# Tactile_SW_v2_0.net
KiCad netlist of a schematic drawn in Altium Designer
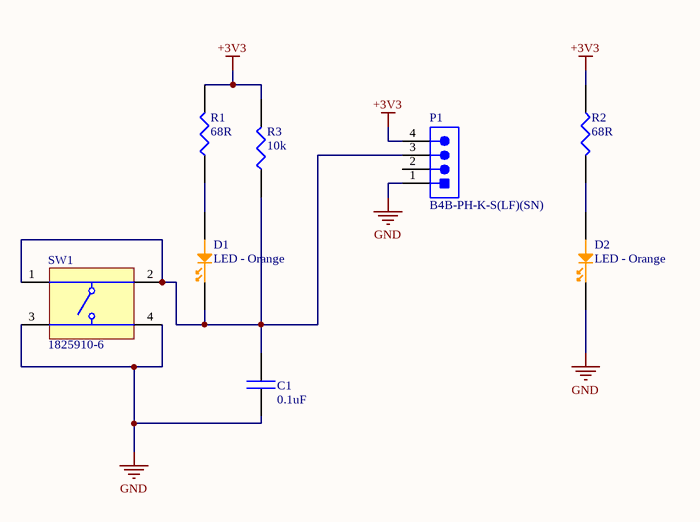
[diagram p0: Tactile SW v2.0.SchDoc]

(export (version "E")
  (design (tool "Eeschema 10.0.6"))
  (components
    (comp (ref "C1")
      (value "0.1uF")
      (footprint "0.1uF 0603")
      (description "CAP CER 0.1UF 16V X7R 0603")
      (fields
        (field (name "MANUFACTURER") "KEMET")
        (field (name "MANUFACTURER PART NUMBER") "C0603C104M4RACTU")
      )
      (libsource (lib "Limit_Switch") (part "C0603C104M4RACTU"))
    )
    (comp (ref "D1")
      (value "LED - Orange")
      (footprint "LED0603-Orange")
      (description "LED ORANGE CLEAR SMD")
      (fields
        (field (name "MANUFACTURER") "Vishay Lite-On")
        (field (name "MANUFACTURER PART NUMBER") "LTST-C191KFKT")
      )
      (libsource (lib "Limit_Switch") (part "LTST-C191KFKT"))
    )
    (comp (ref "D2")
      (value "LED - Orange")
      (footprint "LED0603-Orange")
      (description "LED ORANGE CLEAR SMD")
      (fields
        (field (name "MANUFACTURER") "Vishay Lite-On")
        (field (name "MANUFACTURER PART NUMBER") "LTST-C191KFKT")
      )
      (libsource (lib "Limit_Switch") (part "LTST-C191KFKT"))
    )
    (comp (ref "P1")
      (value "B4B-PH-K-S(LF)(SN)")
      (footprint "JST-B4B-PH-K-S_V")
      (fields (field (name "MANUFACTURER") "JST"))
      (libsource (lib "Altium Content Vault") (part "CN-1P-M-R4"))
    )
    (comp (ref "R1")
      (value "68R")
      (footprint "68R 0603")
      (description "CRGP 0603 68R 1%")
      (fields
        (field (name "MANUFACTURER") "TE Connectivity")
        (field (name "MANUFACTURER PART NUMBER") "CRGP0603F68R")
      )
      (libsource (lib "Limit_Switch") (part "CRGP0603F68R"))
    )
    (comp (ref "R2")
      (value "68R")
      (footprint "68R 0603")
      (description "CRGP 0603 68R 1%")
      (fields
        (field (name "MANUFACTURER") "TE Connectivity")
        (field (name "MANUFACTURER PART NUMBER") "CRGP0603F68R")
      )
      (libsource (lib "Limit_Switch") (part "CRGP0603F68R"))
    )
    (comp (ref "R3")
      (value "10k")
      (footprint "10k R0603")
      (description "RES 10.0K OHM 1/10W 1% 0603")
      (fields
        (field (name "MANUFACTURER") "TE Connectivity")
        (field (name "MANUFACTURER PART NUMBER") "CRG0603F10K/10")
      )
      (libsource (lib "Limit_Switch") (part "CRG0603F10K/10"))
    )
    (comp (ref "SW1")
      (value "1825910-6")
      (footprint "TECO-1825910-6_V")
      (description "Tact Switch, SPST-NO, 0.05 A, -35 to 85 degC, 4-Pin THD, RoHS, Bulk")
      (fields (field (name "MANUFACTURER") "TE Connectivity"))
      (libsource (lib "Altium Content Vault") (part "SW-SPST-4_A"))
    )
  )
  (nets
    (net (code "1") (name "+3V3") (class "Default")
      (node (ref "P1") (pin "4") (pinfunction "4_4") (pintype "passive"))
      (node (ref "R1") (pin "2") (pinfunction "2_2") (pintype "passive"))
      (node (ref "R2") (pin "1") (pinfunction "1_1") (pintype "passive"))
      (node (ref "R3") (pin "2") (pinfunction "2_2") (pintype "passive"))
    )
    (net (code "2") (name "GND") (class "Default")
      (node (ref "C1") (pin "1") (pinfunction "1_1") (pintype "passive"))
      (node (ref "D2") (pin "1") (pinfunction "Cathode_1") (pintype "passive"))
      (node (ref "P1") (pin "1") (pinfunction "1_1") (pintype "passive"))
      (node (ref "SW1") (pin "3") (pinfunction "3_3") (pintype "passive"))
      (node (ref "SW1") (pin "4") (pinfunction "4_4") (pintype "passive"))
    )
    (net (code "3") (name "Net-(D1-Anode)") (class "Default")
      (node (ref "D1") (pin "2") (pinfunction "Anode_2") (pintype "passive"))
      (node (ref "R1") (pin "1") (pinfunction "1_1") (pintype "passive"))
    )
    (net (code "4") (name "Net-(D1-Cathode)") (class "Default")
      (node (ref "C1") (pin "2") (pinfunction "2_2") (pintype "passive"))
      (node (ref "D1") (pin "1") (pinfunction "Cathode_1") (pintype "passive"))
      (node (ref "P1") (pin "3") (pinfunction "3_3") (pintype "passive"))
      (node (ref "R3") (pin "1") (pinfunction "1_1") (pintype "passive"))
      (node (ref "SW1") (pin "1") (pinfunction "1_1") (pintype "passive"))
      (node (ref "SW1") (pin "2") (pinfunction "2_2") (pintype "passive"))
    )
    (net (code "5") (name "Net-(D2-Anode)") (class "Default")
      (node (ref "D2") (pin "2") (pinfunction "Anode_2") (pintype "passive"))
      (node (ref "R2") (pin "2") (pinfunction "2_2") (pintype "passive"))
    )
    (net (code "6") (name "unconnected-(P1-Pad2)") (class "Default")
      (node (ref "P1") (pin "2") (pinfunction "2_2") (pintype "passive"))
    )
  )
)
